# Driver_Board.net
KiCad netlist of a schematic drawn in EAGLE
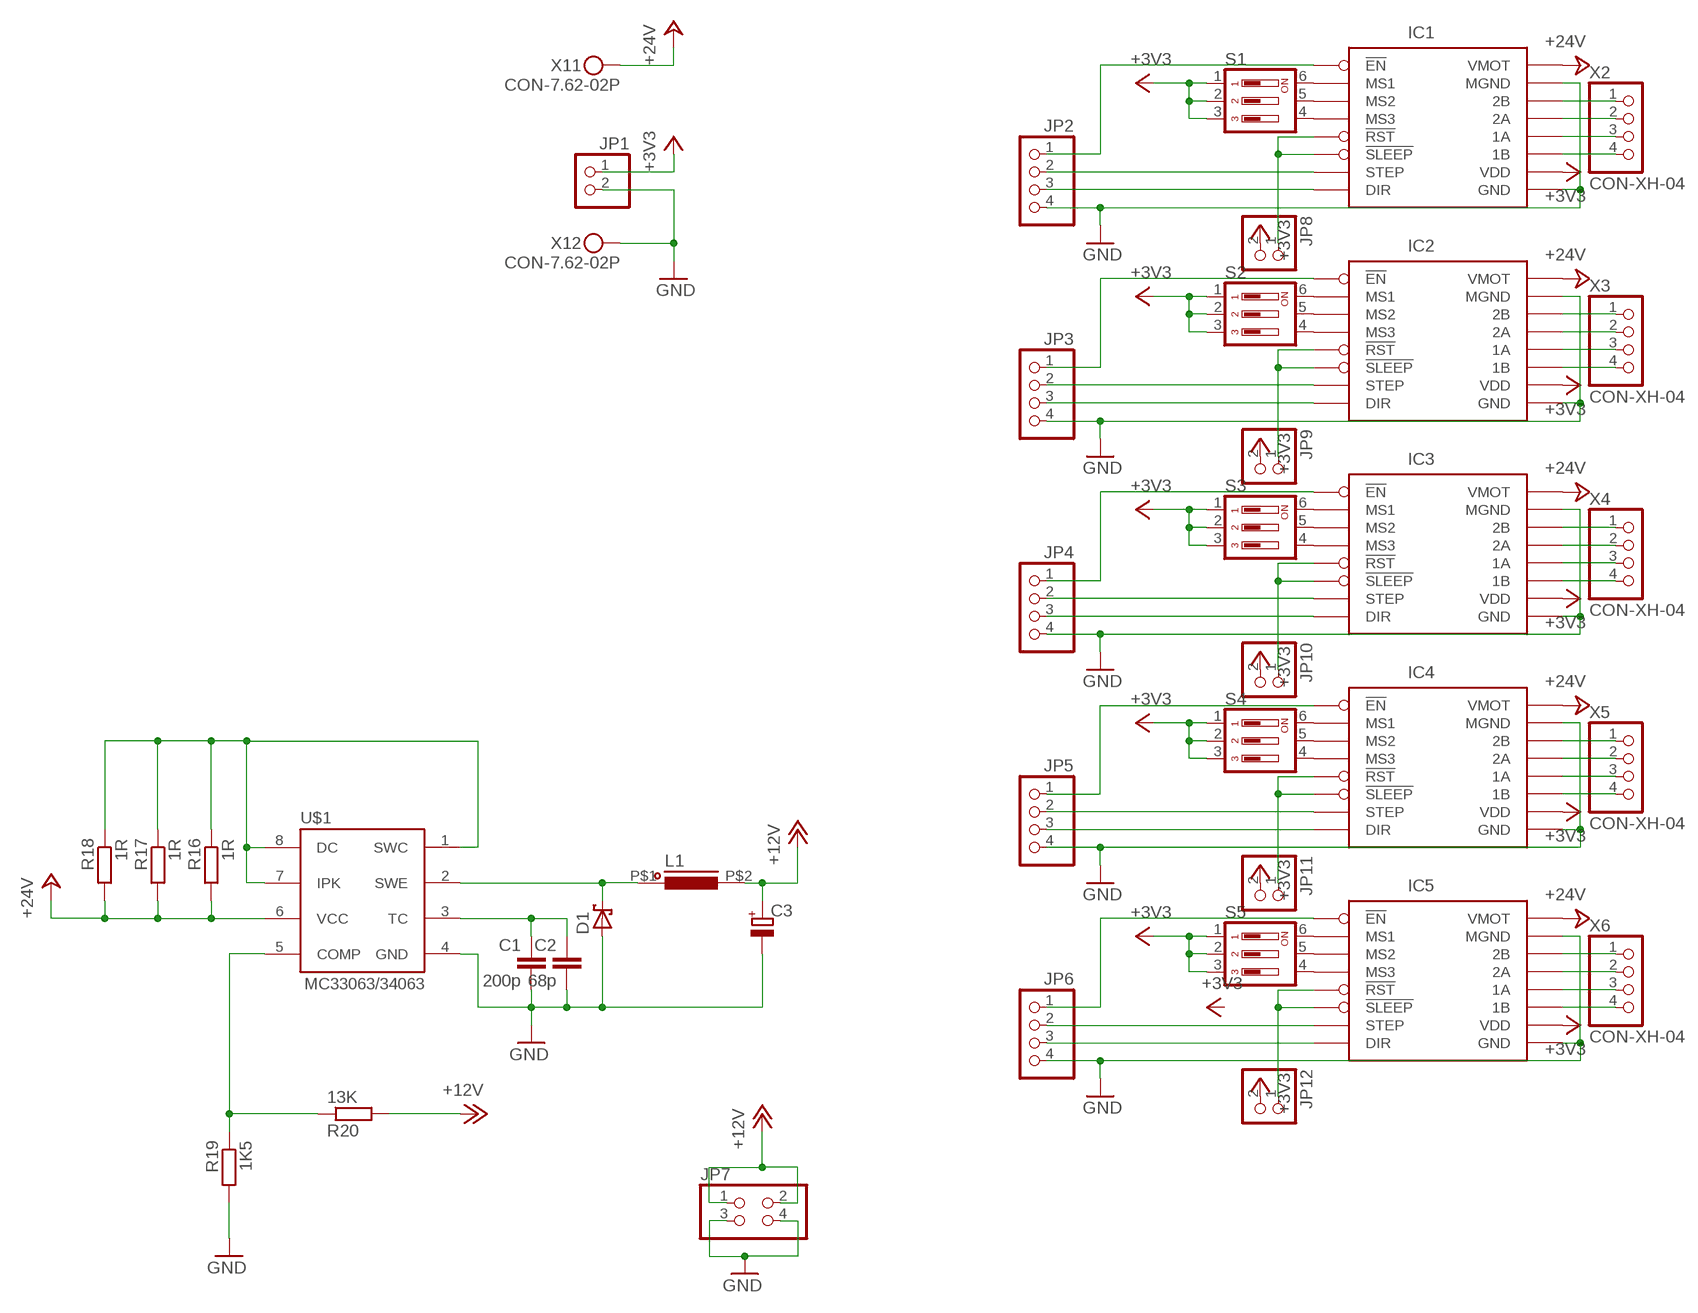
[diagram p0: schematic, sheet 1]

(export (version "E")
  (design (tool "Eeschema 10.0.6"))
  (components
    (comp (ref "C1")
      (value "200p")
      (footprint "eagle-import:C0805")
      (libsource (lib "eagle-import") (part "CAP_0805"))
    )
    (comp (ref "C2")
      (value "68p")
      (footprint "eagle-import:C0805")
      (libsource (lib "eagle-import") (part "CAP_0805"))
    )
    (comp (ref "C3")
      (value "CAP-POL_E3.5-8")
      (footprint "eagle-import:E3,5-8")
      (libsource (lib "eagle-import") (part "CAP-POL_E3.5-8"))
    )
    (comp (ref "D1")
      (value "DIODE-SH_SMA")
      (footprint "eagle-import:DO214AC")
      (libsource (lib "eagle-import") (part "DIODE-SH_SMA"))
    )
    (comp (ref "IC1")
      (value "STEP-DRV")
      (footprint "eagle-import:DRV-BRK")
      (libsource (lib "eagle-import") (part "STEP-DRV"))
    )
    (comp (ref "IC2")
      (value "STEP-DRV")
      (footprint "eagle-import:DRV-BRK")
      (libsource (lib "eagle-import") (part "STEP-DRV"))
    )
    (comp (ref "IC3")
      (value "STEP-DRV")
      (footprint "eagle-import:DRV-BRK")
      (libsource (lib "eagle-import") (part "STEP-DRV"))
    )
    (comp (ref "IC4")
      (value "STEP-DRV")
      (footprint "eagle-import:DRV-BRK")
      (libsource (lib "eagle-import") (part "STEP-DRV"))
    )
    (comp (ref "IC5")
      (value "STEP-DRV")
      (footprint "eagle-import:DRV-BRK")
      (libsource (lib "eagle-import") (part "STEP-DRV"))
    )
    (comp (ref "JP1")
      (value "PINHD-1X2")
      (footprint "eagle-import:1X02")
      (libsource (lib "eagle-import") (part "PINHD-1X2"))
    )
    (comp (ref "JP2")
      (value "PINHD-1X4")
      (footprint "eagle-import:1X04")
      (libsource (lib "eagle-import") (part "PINHD-1X4"))
    )
    (comp (ref "JP3")
      (value "PINHD-1X4")
      (footprint "eagle-import:1X04")
      (libsource (lib "eagle-import") (part "PINHD-1X4"))
    )
    (comp (ref "JP4")
      (value "PINHD-1X4")
      (footprint "eagle-import:1X04")
      (libsource (lib "eagle-import") (part "PINHD-1X4"))
    )
    (comp (ref "JP5")
      (value "PINHD-1X4")
      (footprint "eagle-import:1X04")
      (libsource (lib "eagle-import") (part "PINHD-1X4"))
    )
    (comp (ref "JP6")
      (value "PINHD-1X4")
      (footprint "eagle-import:1X04")
      (libsource (lib "eagle-import") (part "PINHD-1X4"))
    )
    (comp (ref "JP7")
      (value "PINHD-2X2")
      (footprint "eagle-import:2X02")
      (libsource (lib "eagle-import") (part "PINHD-2X2"))
    )
    (comp (ref "JP8")
      (value "PINHD-1X2")
      (footprint "eagle-import:1X02")
      (libsource (lib "eagle-import") (part "PINHD-1X2"))
    )
    (comp (ref "JP9")
      (value "PINHD-1X2")
      (footprint "eagle-import:1X02")
      (libsource (lib "eagle-import") (part "PINHD-1X2"))
    )
    (comp (ref "JP10")
      (value "PINHD-1X2")
      (footprint "eagle-import:1X02")
      (libsource (lib "eagle-import") (part "PINHD-1X2"))
    )
    (comp (ref "JP11")
      (value "PINHD-1X2")
      (footprint "eagle-import:1X02")
      (libsource (lib "eagle-import") (part "PINHD-1X2"))
    )
    (comp (ref "JP12")
      (value "PINHD-1X2")
      (footprint "eagle-import:1X02")
      (libsource (lib "eagle-import") (part "PINHD-1X2"))
    )
    (comp (ref "L1")
      (value "INDUCTORCW68")
      (footprint "eagle-import:CW68")
      (libsource (lib "eagle-import") (part "INDUCTORCW68"))
    )
    (comp (ref "R16")
      (value "1R")
      (footprint "eagle-import:R0805")
      (libsource (lib "eagle-import") (part "R_0805"))
    )
    (comp (ref "R17")
      (value "1R")
      (footprint "eagle-import:R0805")
      (libsource (lib "eagle-import") (part "R_0805"))
    )
    (comp (ref "R18")
      (value "1R")
      (footprint "eagle-import:R0805")
      (libsource (lib "eagle-import") (part "R_0805"))
    )
    (comp (ref "R19")
      (value "1K5")
      (footprint "eagle-import:R0805")
      (libsource (lib "eagle-import") (part "R_0805"))
    )
    (comp (ref "R20")
      (value "13K")
      (footprint "eagle-import:R0805")
      (libsource (lib "eagle-import") (part "R_0805"))
    )
    (comp (ref "S1")
      (value "SW-DIP03S")
      (footprint "eagle-import:DIP03YL")
      (libsource (lib "eagle-import") (part "SW-DIP03S"))
    )
    (comp (ref "S2")
      (value "SW-DIP03S")
      (footprint "eagle-import:DIP03YL")
      (libsource (lib "eagle-import") (part "SW-DIP03S"))
    )
    (comp (ref "S3")
      (value "SW-DIP03S")
      (footprint "eagle-import:DIP03YL")
      (libsource (lib "eagle-import") (part "SW-DIP03S"))
    )
    (comp (ref "S4")
      (value "SW-DIP03S")
      (footprint "eagle-import:DIP03YL")
      (libsource (lib "eagle-import") (part "SW-DIP03S"))
    )
    (comp (ref "S5")
      (value "SW-DIP03S")
      (footprint "eagle-import:DIP03YL")
      (libsource (lib "eagle-import") (part "SW-DIP03S"))
    )
    (comp (ref "U$1")
      (value "MC33063/MC34063P")
      (footprint "eagle-import:DIL08")
      (libsource (lib "eagle-import") (part "MC33063/MC34063P"))
    )
    (comp (ref "X1")
      (value "CON-7.62-02P")
      (footprint "eagle-import:KF25C-7.62-02P-13")
      (libsource (lib "eagle-import") (part "CON-7.62-02P"))
    )
    (comp (ref "X2")
      (value "CON-XH-04")
      (footprint "eagle-import:XH-04")
      (libsource (lib "eagle-import") (part "CON-XH-04"))
    )
    (comp (ref "X3")
      (value "CON-XH-04")
      (footprint "eagle-import:XH-04")
      (libsource (lib "eagle-import") (part "CON-XH-04"))
    )
    (comp (ref "X4")
      (value "CON-XH-04")
      (footprint "eagle-import:XH-04")
      (libsource (lib "eagle-import") (part "CON-XH-04"))
    )
    (comp (ref "X5")
      (value "CON-XH-04")
      (footprint "eagle-import:XH-04")
      (libsource (lib "eagle-import") (part "CON-XH-04"))
    )
    (comp (ref "X6")
      (value "CON-XH-04")
      (footprint "eagle-import:XH-04")
      (libsource (lib "eagle-import") (part "CON-XH-04"))
    )
  )
  (nets
    (net (code "1") (name "+3V3") (class "Default")
      (node (ref "IC1") (pin "P$10") (pinfunction "VDD_P$10") (pintype "bidirectional"))
      (node (ref "IC2") (pin "P$10") (pinfunction "VDD_P$10") (pintype "bidirectional"))
      (node (ref "IC3") (pin "P$10") (pinfunction "VDD_P$10") (pintype "bidirectional"))
      (node (ref "IC4") (pin "P$10") (pinfunction "VDD_P$10") (pintype "bidirectional"))
      (node (ref "IC5") (pin "P$10") (pinfunction "VDD_P$10") (pintype "bidirectional"))
      (node (ref "JP1") (pin "1") (pinfunction "1_1") (pintype "passive"))
      (node (ref "JP10") (pin "2") (pinfunction "2_2") (pintype "passive"))
      (node (ref "JP11") (pin "2") (pinfunction "2_2") (pintype "passive"))
      (node (ref "JP12") (pin "2") (pinfunction "2_2") (pintype "passive"))
      (node (ref "JP8") (pin "2") (pinfunction "2_2") (pintype "passive"))
      (node (ref "JP9") (pin "2") (pinfunction "2_2") (pintype "passive"))
      (node (ref "S1") (pin "1") (pinfunction "1_1") (pintype "passive"))
      (node (ref "S1") (pin "2") (pinfunction "2_2") (pintype "passive"))
      (node (ref "S1") (pin "3") (pinfunction "3_3") (pintype "passive"))
      (node (ref "S2") (pin "1") (pinfunction "1_1") (pintype "passive"))
      (node (ref "S2") (pin "2") (pinfunction "2_2") (pintype "passive"))
      (node (ref "S2") (pin "3") (pinfunction "3_3") (pintype "passive"))
      (node (ref "S3") (pin "1") (pinfunction "1_1") (pintype "passive"))
      (node (ref "S3") (pin "2") (pinfunction "2_2") (pintype "passive"))
      (node (ref "S3") (pin "3") (pinfunction "3_3") (pintype "passive"))
      (node (ref "S4") (pin "1") (pinfunction "1_1") (pintype "passive"))
      (node (ref "S4") (pin "2") (pinfunction "2_2") (pintype "passive"))
      (node (ref "S4") (pin "3") (pinfunction "3_3") (pintype "passive"))
      (node (ref "S5") (pin "1") (pinfunction "1_1") (pintype "passive"))
      (node (ref "S5") (pin "2") (pinfunction "2_2") (pintype "passive"))
      (node (ref "S5") (pin "3") (pinfunction "3_3") (pintype "passive"))
    )
    (net (code "2") (name "+12V") (class "Default")
      (node (ref "C3") (pin "+") (pinfunction "+_+") (pintype "passive"))
      (node (ref "JP7") (pin "1") (pinfunction "1_1") (pintype "passive"))
      (node (ref "JP7") (pin "2") (pinfunction "2_2") (pintype "passive"))
      (node (ref "L1") (pin "P$2") (pinfunction "2_P$2") (pintype "passive"))
      (node (ref "R20") (pin "2") (pinfunction "2_2") (pintype "passive"))
    )
    (net (code "3") (name "+24V") (class "Default")
      (node (ref "IC1") (pin "P$16") (pinfunction "VMOT_P$16") (pintype "bidirectional"))
      (node (ref "IC2") (pin "P$16") (pinfunction "VMOT_P$16") (pintype "bidirectional"))
      (node (ref "IC3") (pin "P$16") (pinfunction "VMOT_P$16") (pintype "bidirectional"))
      (node (ref "IC4") (pin "P$16") (pinfunction "VMOT_P$16") (pintype "bidirectional"))
      (node (ref "IC5") (pin "P$16") (pinfunction "VMOT_P$16") (pintype "bidirectional"))
      (node (ref "R16") (pin "2") (pinfunction "2_2") (pintype "passive"))
      (node (ref "R17") (pin "2") (pinfunction "2_2") (pintype "passive"))
      (node (ref "R18") (pin "2") (pinfunction "2_2") (pintype "passive"))
      (node (ref "U$1") (pin "6") (pinfunction "VCC_6") (pintype "power_in"))
      (node (ref "X1") (pin "P$1") (pinfunction "KL_P$1") (pintype "passive"))
    )
    (net (code "4") (name "GND") (class "Default")
      (node (ref "C1") (pin "2") (pinfunction "2_2") (pintype "passive"))
      (node (ref "C2") (pin "2") (pinfunction "2_2") (pintype "passive"))
      (node (ref "C3") (pin "-") (pinfunction "-_-") (pintype "passive"))
      (node (ref "D1") (pin "A") (pinfunction "A_A") (pintype "passive"))
      (node (ref "IC1") (pin "P$15") (pinfunction "MGND_P$15") (pintype "bidirectional"))
      (node (ref "IC1") (pin "P$9") (pinfunction "GND_P$9") (pintype "bidirectional"))
      (node (ref "IC2") (pin "P$15") (pinfunction "MGND_P$15") (pintype "bidirectional"))
      (node (ref "IC2") (pin "P$9") (pinfunction "GND_P$9") (pintype "bidirectional"))
      (node (ref "IC3") (pin "P$15") (pinfunction "MGND_P$15") (pintype "bidirectional"))
      (node (ref "IC3") (pin "P$9") (pinfunction "GND_P$9") (pintype "bidirectional"))
      (node (ref "IC4") (pin "P$15") (pinfunction "MGND_P$15") (pintype "bidirectional"))
      (node (ref "IC4") (pin "P$9") (pinfunction "GND_P$9") (pintype "bidirectional"))
      (node (ref "IC5") (pin "P$15") (pinfunction "MGND_P$15") (pintype "bidirectional"))
      (node (ref "IC5") (pin "P$9") (pinfunction "GND_P$9") (pintype "bidirectional"))
      (node (ref "JP1") (pin "2") (pinfunction "2_2") (pintype "passive"))
      (node (ref "JP2") (pin "4") (pinfunction "4_4") (pintype "passive"))
      (node (ref "JP3") (pin "4") (pinfunction "4_4") (pintype "passive"))
      (node (ref "JP4") (pin "4") (pinfunction "4_4") (pintype "passive"))
      (node (ref "JP5") (pin "4") (pinfunction "4_4") (pintype "passive"))
      (node (ref "JP6") (pin "4") (pinfunction "4_4") (pintype "passive"))
      (node (ref "JP7") (pin "3") (pinfunction "3_3") (pintype "passive"))
      (node (ref "JP7") (pin "4") (pinfunction "4_4") (pintype "passive"))
      (node (ref "R19") (pin "2") (pinfunction "2_2") (pintype "passive"))
      (node (ref "U$1") (pin "4") (pinfunction "GND_4") (pintype "power_in"))
      (node (ref "X1") (pin "P$2") (pinfunction "KL_P$2") (pintype "passive"))
    )
    (net (code "5") (name "Net-(IC1-1A)") (class "Default")
      (node (ref "IC1") (pin "P$12") (pinfunction "1A_P$12") (pintype "bidirectional"))
      (node (ref "X2") (pin "3") (pinfunction "3_3") (pintype "passive"))
    )
    (net (code "6") (name "Net-(IC1-1B)") (class "Default")
      (node (ref "IC1") (pin "P$11") (pinfunction "1B_P$11") (pintype "bidirectional"))
      (node (ref "X2") (pin "4") (pinfunction "4_4") (pintype "passive"))
    )
    (net (code "7") (name "Net-(IC1-2A)") (class "Default")
      (node (ref "IC1") (pin "P$13") (pinfunction "2A_P$13") (pintype "bidirectional"))
      (node (ref "X2") (pin "2") (pinfunction "2_2") (pintype "passive"))
    )
    (net (code "8") (name "Net-(IC1-2B)") (class "Default")
      (node (ref "IC1") (pin "P$14") (pinfunction "2B_P$14") (pintype "bidirectional"))
      (node (ref "X2") (pin "1") (pinfunction "1_1") (pintype "passive"))
    )
    (net (code "9") (name "Net-(IC1-DIR)") (class "Default")
      (node (ref "IC1") (pin "P$8") (pinfunction "DIR_P$8") (pintype "bidirectional"))
      (node (ref "JP2") (pin "3") (pinfunction "3_3") (pintype "passive"))
    )
    (net (code "10") (name "Net-(IC1-MS1)") (class "Default")
      (node (ref "IC1") (pin "P$2") (pinfunction "MS1_P$2") (pintype "bidirectional"))
      (node (ref "S1") (pin "6") (pinfunction "6_6") (pintype "passive"))
    )
    (net (code "11") (name "Net-(IC1-MS2)") (class "Default")
      (node (ref "IC1") (pin "P$3") (pinfunction "MS2_P$3") (pintype "bidirectional"))
      (node (ref "S1") (pin "5") (pinfunction "5_5") (pintype "passive"))
    )
    (net (code "12") (name "Net-(IC1-MS3)") (class "Default")
      (node (ref "IC1") (pin "P$4") (pinfunction "MS3_P$4") (pintype "bidirectional"))
      (node (ref "S1") (pin "4") (pinfunction "4_4") (pintype "passive"))
    )
    (net (code "13") (name "Net-(IC1-STEP)") (class "Default")
      (node (ref "IC1") (pin "P$7") (pinfunction "STEP_P$7") (pintype "bidirectional"))
      (node (ref "JP2") (pin "2") (pinfunction "2_2") (pintype "passive"))
    )
    (net (code "14") (name "Net-(IC1-~{EN})") (class "Default")
      (node (ref "IC1") (pin "P$1") (pinfunction "~{EN}_P$1") (pintype "bidirectional"))
      (node (ref "JP2") (pin "1") (pinfunction "1_1") (pintype "passive"))
    )
    (net (code "15") (name "Net-(IC1-~{RST})") (class "Default")
      (node (ref "IC1") (pin "P$5") (pinfunction "~{RST}_P$5") (pintype "bidirectional"))
      (node (ref "IC1") (pin "P$6") (pinfunction "~{SLEEP}_P$6") (pintype "bidirectional"))
      (node (ref "JP8") (pin "1") (pinfunction "1_1") (pintype "passive"))
    )
    (net (code "16") (name "Net-(IC2-1A)") (class "Default")
      (node (ref "IC2") (pin "P$12") (pinfunction "1A_P$12") (pintype "bidirectional"))
      (node (ref "X3") (pin "3") (pinfunction "3_3") (pintype "passive"))
    )
    (net (code "17") (name "Net-(IC2-1B)") (class "Default")
      (node (ref "IC2") (pin "P$11") (pinfunction "1B_P$11") (pintype "bidirectional"))
      (node (ref "X3") (pin "4") (pinfunction "4_4") (pintype "passive"))
    )
    (net (code "18") (name "Net-(IC2-2A)") (class "Default")
      (node (ref "IC2") (pin "P$13") (pinfunction "2A_P$13") (pintype "bidirectional"))
      (node (ref "X3") (pin "2") (pinfunction "2_2") (pintype "passive"))
    )
    (net (code "19") (name "Net-(IC2-2B)") (class "Default")
      (node (ref "IC2") (pin "P$14") (pinfunction "2B_P$14") (pintype "bidirectional"))
      (node (ref "X3") (pin "1") (pinfunction "1_1") (pintype "passive"))
    )
    (net (code "20") (name "Net-(IC2-DIR)") (class "Default")
      (node (ref "IC2") (pin "P$8") (pinfunction "DIR_P$8") (pintype "bidirectional"))
      (node (ref "JP3") (pin "3") (pinfunction "3_3") (pintype "passive"))
    )
    (net (code "21") (name "Net-(IC2-MS1)") (class "Default")
      (node (ref "IC2") (pin "P$2") (pinfunction "MS1_P$2") (pintype "bidirectional"))
      (node (ref "S2") (pin "6") (pinfunction "6_6") (pintype "passive"))
    )
    (net (code "22") (name "Net-(IC2-MS2)") (class "Default")
      (node (ref "IC2") (pin "P$3") (pinfunction "MS2_P$3") (pintype "bidirectional"))
      (node (ref "S2") (pin "5") (pinfunction "5_5") (pintype "passive"))
    )
    (net (code "23") (name "Net-(IC2-MS3)") (class "Default")
      (node (ref "IC2") (pin "P$4") (pinfunction "MS3_P$4") (pintype "bidirectional"))
      (node (ref "S2") (pin "4") (pinfunction "4_4") (pintype "passive"))
    )
    (net (code "24") (name "Net-(IC2-STEP)") (class "Default")
      (node (ref "IC2") (pin "P$7") (pinfunction "STEP_P$7") (pintype "bidirectional"))
      (node (ref "JP3") (pin "2") (pinfunction "2_2") (pintype "passive"))
    )
    (net (code "25") (name "Net-(IC2-~{EN})") (class "Default")
      (node (ref "IC2") (pin "P$1") (pinfunction "~{EN}_P$1") (pintype "bidirectional"))
      (node (ref "JP3") (pin "1") (pinfunction "1_1") (pintype "passive"))
    )
    (net (code "26") (name "Net-(IC2-~{RST})") (class "Default")
      (node (ref "IC2") (pin "P$5") (pinfunction "~{RST}_P$5") (pintype "bidirectional"))
      (node (ref "IC2") (pin "P$6") (pinfunction "~{SLEEP}_P$6") (pintype "bidirectional"))
      (node (ref "JP9") (pin "1") (pinfunction "1_1") (pintype "passive"))
    )
    (net (code "27") (name "Net-(IC3-1A)") (class "Default")
      (node (ref "IC3") (pin "P$12") (pinfunction "1A_P$12") (pintype "bidirectional"))
      (node (ref "X4") (pin "3") (pinfunction "3_3") (pintype "passive"))
    )
    (net (code "28") (name "Net-(IC3-1B)") (class "Default")
      (node (ref "IC3") (pin "P$11") (pinfunction "1B_P$11") (pintype "bidirectional"))
      (node (ref "X4") (pin "4") (pinfunction "4_4") (pintype "passive"))
    )
    (net (code "29") (name "Net-(IC3-2A)") (class "Default")
      (node (ref "IC3") (pin "P$13") (pinfunction "2A_P$13") (pintype "bidirectional"))
      (node (ref "X4") (pin "2") (pinfunction "2_2") (pintype "passive"))
    )
    (net (code "30") (name "Net-(IC3-2B)") (class "Default")
      (node (ref "IC3") (pin "P$14") (pinfunction "2B_P$14") (pintype "bidirectional"))
      (node (ref "X4") (pin "1") (pinfunction "1_1") (pintype "passive"))
    )
    (net (code "31") (name "Net-(IC3-DIR)") (class "Default")
      (node (ref "IC3") (pin "P$8") (pinfunction "DIR_P$8") (pintype "bidirectional"))
      (node (ref "JP4") (pin "3") (pinfunction "3_3") (pintype "passive"))
    )
    (net (code "32") (name "Net-(IC3-MS1)") (class "Default")
      (node (ref "IC3") (pin "P$2") (pinfunction "MS1_P$2") (pintype "bidirectional"))
      (node (ref "S3") (pin "6") (pinfunction "6_6") (pintype "passive"))
    )
    (net (code "33") (name "Net-(IC3-MS2)") (class "Default")
      (node (ref "IC3") (pin "P$3") (pinfunction "MS2_P$3") (pintype "bidirectional"))
      (node (ref "S3") (pin "5") (pinfunction "5_5") (pintype "passive"))
    )
    (net (code "34") (name "Net-(IC3-MS3)") (class "Default")
      (node (ref "IC3") (pin "P$4") (pinfunction "MS3_P$4") (pintype "bidirectional"))
      (node (ref "S3") (pin "4") (pinfunction "4_4") (pintype "passive"))
    )
    (net (code "35") (name "Net-(IC3-STEP)") (class "Default")
      (node (ref "IC3") (pin "P$7") (pinfunction "STEP_P$7") (pintype "bidirectional"))
      (node (ref "JP4") (pin "2") (pinfunction "2_2") (pintype "passive"))
    )
    (net (code "36") (name "Net-(IC3-~{EN})") (class "Default")
      (node (ref "IC3") (pin "P$1") (pinfunction "~{EN}_P$1") (pintype "bidirectional"))
      (node (ref "JP4") (pin "1") (pinfunction "1_1") (pintype "passive"))
    )
    (net (code "37") (name "Net-(IC3-~{RST})") (class "Default")
      (node (ref "IC3") (pin "P$5") (pinfunction "~{RST}_P$5") (pintype "bidirectional"))
      (node (ref "IC3") (pin "P$6") (pinfunction "~{SLEEP}_P$6") (pintype "bidirectional"))
      (node (ref "JP10") (pin "1") (pinfunction "1_1") (pintype "passive"))
    )
    (net (code "38") (name "Net-(IC4-1A)") (class "Default")
      (node (ref "IC4") (pin "P$12") (pinfunction "1A_P$12") (pintype "bidirectional"))
      (node (ref "X5") (pin "3") (pinfunction "3_3") (pintype "passive"))
    )
    (net (code "39") (name "Net-(IC4-1B)") (class "Default")
      (node (ref "IC4") (pin "P$11") (pinfunction "1B_P$11") (pintype "bidirectional"))
      (node (ref "X5") (pin "4") (pinfunction "4_4") (pintype "passive"))
    )
    (net (code "40") (name "Net-(IC4-2A)") (class "Default")
      (node (ref "IC4") (pin "P$13") (pinfunction "2A_P$13") (pintype "bidirectional"))
      (node (ref "X5") (pin "2") (pinfunction "2_2") (pintype "passive"))
    )
    (net (code "41") (name "Net-(IC4-2B)") (class "Default")
      (node (ref "IC4") (pin "P$14") (pinfunction "2B_P$14") (pintype "bidirectional"))
      (node (ref "X5") (pin "1") (pinfunction "1_1") (pintype "passive"))
    )
    (net (code "42") (name "Net-(IC4-DIR)") (class "Default")
      (node (ref "IC4") (pin "P$8") (pinfunction "DIR_P$8") (pintype "bidirectional"))
      (node (ref "JP5") (pin "3") (pinfunction "3_3") (pintype "passive"))
    )
    (net (code "43") (name "Net-(IC4-MS1)") (class "Default")
      (node (ref "IC4") (pin "P$2") (pinfunction "MS1_P$2") (pintype "bidirectional"))
      (node (ref "S4") (pin "6") (pinfunction "6_6") (pintype "passive"))
    )
    (net (code "44") (name "Net-(IC4-MS2)") (class "Default")
      (node (ref "IC4") (pin "P$3") (pinfunction "MS2_P$3") (pintype "bidirectional"))
      (node (ref "S4") (pin "5") (pinfunction "5_5") (pintype "passive"))
    )
    (net (code "45") (name "Net-(IC4-MS3)") (class "Default")
      (node (ref "IC4") (pin "P$4") (pinfunction "MS3_P$4") (pintype "bidirectional"))
      (node (ref "S4") (pin "4") (pinfunction "4_4") (pintype "passive"))
    )
    (net (code "46") (name "Net-(IC4-STEP)") (class "Default")
      (node (ref "IC4") (pin "P$7") (pinfunction "STEP_P$7") (pintype "bidirectional"))
      (node (ref "JP5") (pin "2") (pinfunction "2_2") (pintype "passive"))
    )
    (net (code "47") (name "Net-(IC4-~{EN})") (class "Default")
      (node (ref "IC4") (pin "P$1") (pinfunction "~{EN}_P$1") (pintype "bidirectional"))
      (node (ref "JP5") (pin "1") (pinfunction "1_1") (pintype "passive"))
    )
    (net (code "48") (name "Net-(IC4-~{RST})") (class "Default")
      (node (ref "IC4") (pin "P$5") (pinfunction "~{RST}_P$5") (pintype "bidirectional"))
      (node (ref "IC4") (pin "P$6") (pinfunction "~{SLEEP}_P$6") (pintype "bidirectional"))
      (node (ref "JP11") (pin "1") (pinfunction "1_1") (pintype "passive"))
    )
    (net (code "49") (name "Net-(IC5-1A)") (class "Default")
      (node (ref "IC5") (pin "P$12") (pinfunction "1A_P$12") (pintype "bidirectional"))
      (node (ref "X6") (pin "3") (pinfunction "3_3") (pintype "passive"))
    )
    (net (code "50") (name "Net-(IC5-1B)") (class "Default")
      (node (ref "IC5") (pin "P$11") (pinfunction "1B_P$11") (pintype "bidirectional"))
      (node (ref "X6") (pin "4") (pinfunction "4_4") (pintype "passive"))
    )
    (net (code "51") (name "Net-(IC5-2A)") (class "Default")
      (node (ref "IC5") (pin "P$13") (pinfunction "2A_P$13") (pintype "bidirectional"))
      (node (ref "X6") (pin "2") (pinfunction "2_2") (pintype "passive"))
    )
    (net (code "52") (name "Net-(IC5-2B)") (class "Default")
      (node (ref "IC5") (pin "P$14") (pinfunction "2B_P$14") (pintype "bidirectional"))
      (node (ref "X6") (pin "1") (pinfunction "1_1") (pintype "passive"))
    )
    (net (code "53") (name "Net-(IC5-DIR)") (class "Default")
      (node (ref "IC5") (pin "P$8") (pinfunction "DIR_P$8") (pintype "bidirectional"))
      (node (ref "JP6") (pin "3") (pinfunction "3_3") (pintype "passive"))
    )
    (net (code "54") (name "Net-(IC5-MS1)") (class "Default")
      (node (ref "IC5") (pin "P$2") (pinfunction "MS1_P$2") (pintype "bidirectional"))
      (node (ref "S5") (pin "6") (pinfunction "6_6") (pintype "passive"))
    )
    (net (code "55") (name "Net-(IC5-MS2)") (class "Default")
      (node (ref "IC5") (pin "P$3") (pinfunction "MS2_P$3") (pintype "bidirectional"))
      (node (ref "S5") (pin "5") (pinfunction "5_5") (pintype "passive"))
    )
    (net (code "56") (name "Net-(IC5-MS3)") (class "Default")
      (node (ref "IC5") (pin "P$4") (pinfunction "MS3_P$4") (pintype "bidirectional"))
      (node (ref "S5") (pin "4") (pinfunction "4_4") (pintype "passive"))
    )
    (net (code "57") (name "Net-(IC5-STEP)") (class "Default")
      (node (ref "IC5") (pin "P$7") (pinfunction "STEP_P$7") (pintype "bidirectional"))
      (node (ref "JP6") (pin "2") (pinfunction "2_2") (pintype "passive"))
    )
    (net (code "58") (name "Net-(IC5-~{EN})") (class "Default")
      (node (ref "IC5") (pin "P$1") (pinfunction "~{EN}_P$1") (pintype "bidirectional"))
      (node (ref "JP6") (pin "1") (pinfunction "1_1") (pintype "passive"))
    )
    (net (code "59") (name "Net-(IC5-~{RST})") (class "Default")
      (node (ref "IC5") (pin "P$5") (pinfunction "~{RST}_P$5") (pintype "bidirectional"))
      (node (ref "IC5") (pin "P$6") (pinfunction "~{SLEEP}_P$6") (pintype "bidirectional"))
      (node (ref "JP12") (pin "1") (pinfunction "1_1") (pintype "passive"))
    )
    (net (code "60") (name "Net-(L1-1)") (class "Default")
      (node (ref "D1") (pin "C") (pinfunction "C_C") (pintype "passive"))
      (node (ref "L1") (pin "P$1") (pinfunction "1_P$1") (pintype "passive"))
      (node (ref "U$1") (pin "2") (pinfunction "SWE_2") (pintype "input"))
    )
    (net (code "61") (name "Net-(U$1-COMP)") (class "Default")
      (node (ref "R19") (pin "1") (pinfunction "1_1") (pintype "passive"))
      (node (ref "R20") (pin "1") (pinfunction "1_1") (pintype "passive"))
      (node (ref "U$1") (pin "5") (pinfunction "COMP_5") (pintype "input"))
    )
    (net (code "62") (name "Net-(U$1-DC)") (class "Default")
      (node (ref "R16") (pin "1") (pinfunction "1_1") (pintype "passive"))
      (node (ref "R17") (pin "1") (pinfunction "1_1") (pintype "passive"))
      (node (ref "R18") (pin "1") (pinfunction "1_1") (pintype "passive"))
      (node (ref "U$1") (pin "1") (pinfunction "SWC_1") (pintype "input"))
      (node (ref "U$1") (pin "7") (pinfunction "IPK_7") (pintype "bidirectional"))
      (node (ref "U$1") (pin "8") (pinfunction "DC_8") (pintype "input"))
    )
    (net (code "63") (name "Net-(U$1-TC)") (class "Default")
      (node (ref "C1") (pin "1") (pinfunction "1_1") (pintype "passive"))
      (node (ref "C2") (pin "1") (pinfunction "1_1") (pintype "passive"))
      (node (ref "U$1") (pin "3") (pinfunction "TC_3") (pintype "input"))
    )
  )
)
